# D-class.net
KiCad netlist of a schematic drawn in EAGLE
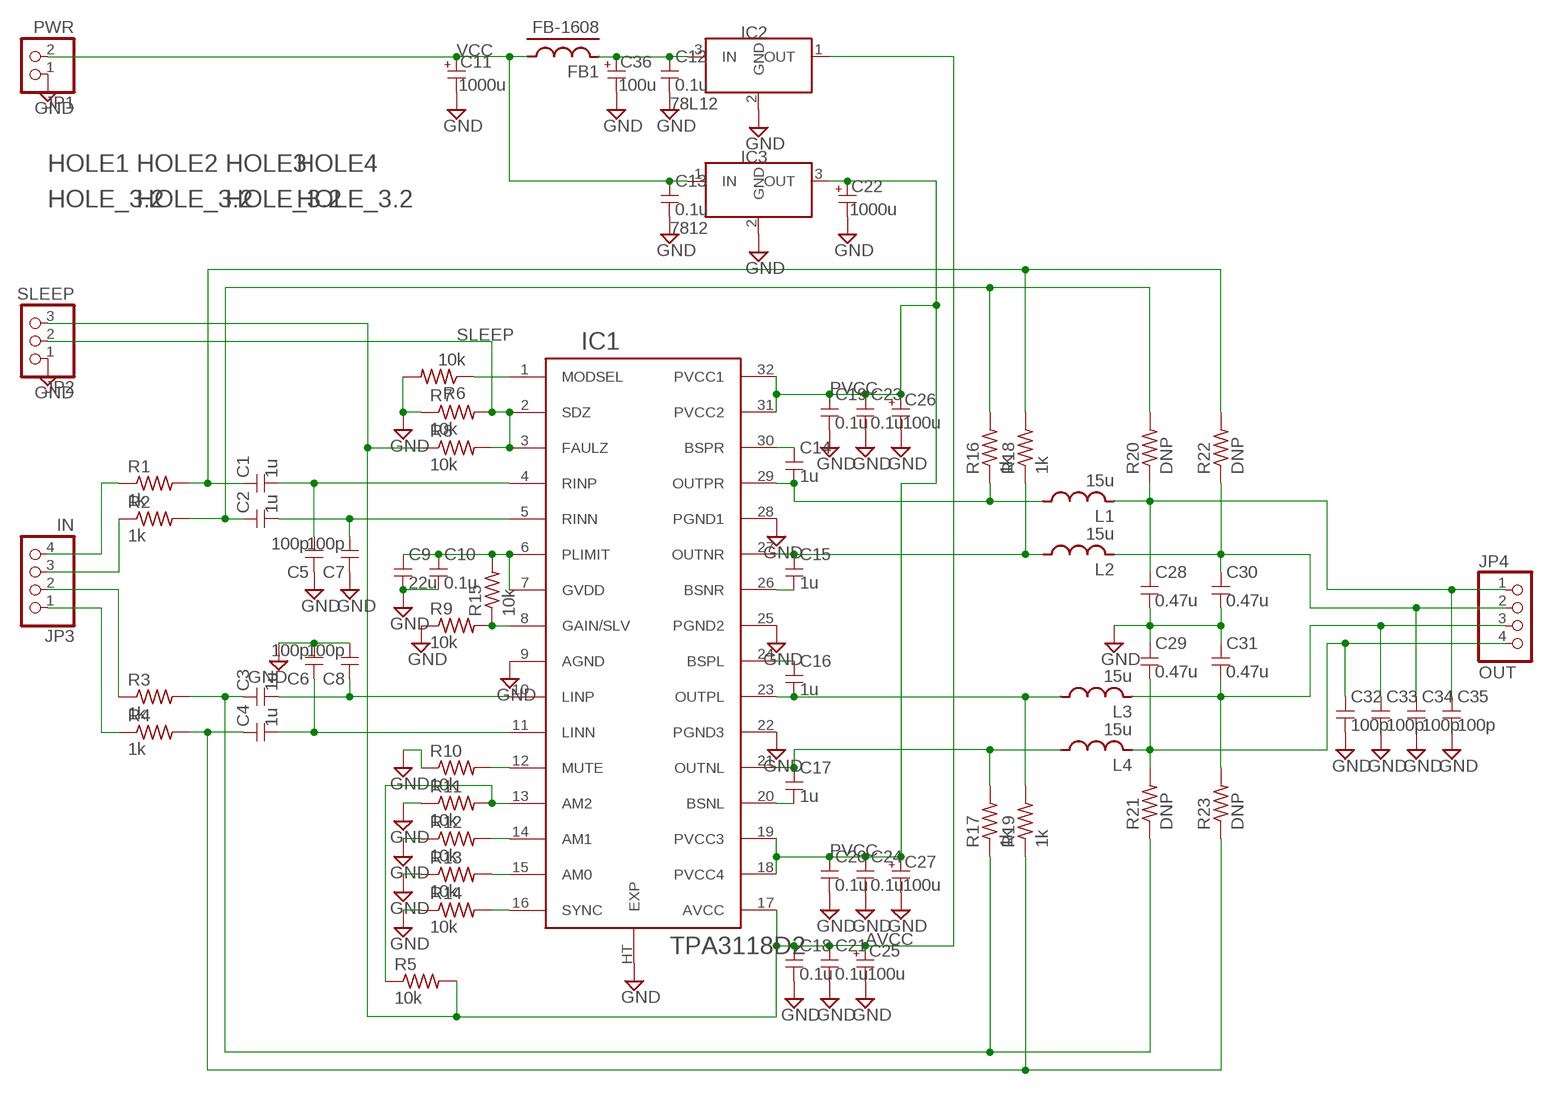
[diagram p0: schematic, sheet 1]

(export (version "E")
  (design (tool "Eeschema 10.0.6"))
  (components
    (comp (ref "C1")
      (value "1u")
      (footprint "eagle-import:3216")
      (libsource (lib "eagle-import") (part "C-3216"))
    )
    (comp (ref "C2")
      (value "1u")
      (footprint "eagle-import:3216")
      (libsource (lib "eagle-import") (part "C-3216"))
    )
    (comp (ref "C3")
      (value "1u")
      (footprint "eagle-import:3216")
      (libsource (lib "eagle-import") (part "C-3216"))
    )
    (comp (ref "C4")
      (value "1u")
      (footprint "eagle-import:3216")
      (libsource (lib "eagle-import") (part "C-3216"))
    )
    (comp (ref "C5")
      (value "100p")
      (footprint "eagle-import:1608")
      (libsource (lib "eagle-import") (part "C-1608"))
    )
    (comp (ref "C6")
      (value "100p")
      (footprint "eagle-import:1608")
      (libsource (lib "eagle-import") (part "C-1608"))
    )
    (comp (ref "C7")
      (value "100p")
      (footprint "eagle-import:1608")
      (libsource (lib "eagle-import") (part "C-1608"))
    )
    (comp (ref "C8")
      (value "100p")
      (footprint "eagle-import:1608")
      (libsource (lib "eagle-import") (part "C-1608"))
    )
    (comp (ref "C9")
      (value "22u")
      (footprint "eagle-import:2012")
      (libsource (lib "eagle-import") (part "C-2012"))
    )
    (comp (ref "C10")
      (value "0.1u")
      (footprint "eagle-import:1608")
      (libsource (lib "eagle-import") (part "C-1608"))
    )
    (comp (ref "C11")
      (value "1000u")
      (footprint "eagle-import:E5-10")
      (libsource (lib "eagle-import") (part "CPOLE5-10"))
    )
    (comp (ref "C12")
      (value "0.1u")
      (footprint "eagle-import:1608")
      (libsource (lib "eagle-import") (part "C-1608"))
    )
    (comp (ref "C13")
      (value "0.1u")
      (footprint "eagle-import:1608")
      (libsource (lib "eagle-import") (part "C-1608"))
    )
    (comp (ref "C14")
      (value "1u")
      (footprint "eagle-import:1608")
      (libsource (lib "eagle-import") (part "C-1608"))
    )
    (comp (ref "C15")
      (value "1u")
      (footprint "eagle-import:1608")
      (libsource (lib "eagle-import") (part "C-1608"))
    )
    (comp (ref "C16")
      (value "1u")
      (footprint "eagle-import:1608")
      (libsource (lib "eagle-import") (part "C-1608"))
    )
    (comp (ref "C17")
      (value "1u")
      (footprint "eagle-import:1608")
      (libsource (lib "eagle-import") (part "C-1608"))
    )
    (comp (ref "C18")
      (value "0.1u")
      (footprint "eagle-import:1608")
      (libsource (lib "eagle-import") (part "C-1608"))
    )
    (comp (ref "C19")
      (value "0.1u")
      (footprint "eagle-import:1608")
      (libsource (lib "eagle-import") (part "C-1608"))
    )
    (comp (ref "C20")
      (value "0.1u")
      (footprint "eagle-import:1608")
      (libsource (lib "eagle-import") (part "C-1608"))
    )
    (comp (ref "C21")
      (value "0.1u")
      (footprint "eagle-import:2012")
      (libsource (lib "eagle-import") (part "C-2012"))
    )
    (comp (ref "C22")
      (value "1000u")
      (footprint "eagle-import:E5-10")
      (libsource (lib "eagle-import") (part "CPOLE5-10"))
    )
    (comp (ref "C23")
      (value "0.1u")
      (footprint "eagle-import:2012")
      (libsource (lib "eagle-import") (part "C-2012"))
    )
    (comp (ref "C24")
      (value "0.1u")
      (footprint "eagle-import:2012")
      (libsource (lib "eagle-import") (part "C-2012"))
    )
    (comp (ref "C25")
      (value "100u")
      (footprint "eagle-import:E2.5-6.5")
      (libsource (lib "eagle-import") (part "CPOLE2.5-6.5"))
    )
    (comp (ref "C26")
      (value "100u")
      (footprint "eagle-import:E2.5-6.5")
      (libsource (lib "eagle-import") (part "CPOLE2.5-6.5"))
    )
    (comp (ref "C27")
      (value "100u")
      (footprint "eagle-import:E2.5-6.5")
      (libsource (lib "eagle-import") (part "CPOLE2.5-6.5"))
    )
    (comp (ref "C28")
      (value "0.47u")
      (footprint "eagle-import:C050-030X075")
      (libsource (lib "eagle-import") (part "C-5"))
    )
    (comp (ref "C29")
      (value "0.47u")
      (footprint "eagle-import:C050-030X075")
      (libsource (lib "eagle-import") (part "C-5"))
    )
    (comp (ref "C30")
      (value "0.47u")
      (footprint "eagle-import:C050-030X075")
      (libsource (lib "eagle-import") (part "C-5"))
    )
    (comp (ref "C31")
      (value "0.47u")
      (footprint "eagle-import:C050-030X075")
      (libsource (lib "eagle-import") (part "C-5"))
    )
    (comp (ref "C32")
      (value "100p")
      (footprint "eagle-import:1608")
      (libsource (lib "eagle-import") (part "C-1608"))
    )
    (comp (ref "C33")
      (value "100p")
      (footprint "eagle-import:1608")
      (libsource (lib "eagle-import") (part "C-1608"))
    )
    (comp (ref "C34")
      (value "100p")
      (footprint "eagle-import:1608")
      (libsource (lib "eagle-import") (part "C-1608"))
    )
    (comp (ref "C35")
      (value "100p")
      (footprint "eagle-import:1608")
      (libsource (lib "eagle-import") (part "C-1608"))
    )
    (comp (ref "C36")
      (value "100u")
      (footprint "eagle-import:E2.5-6.5")
      (libsource (lib "eagle-import") (part "CPOLE2.5-6.5"))
    )
    (comp (ref "FB1")
      (value "FB-1608")
      (footprint "eagle-import:1608")
      (libsource (lib "eagle-import") (part "FB-1608"))
    )
    (comp (ref "HOLE1")
      (value "HOLE_3.2")
      (footprint "eagle-import:HOLE_3.2")
      (libsource (lib "eagle-import") (part "HOLE_3.2"))
    )
    (comp (ref "HOLE2")
      (value "HOLE_3.2")
      (footprint "eagle-import:HOLE_3.2")
      (libsource (lib "eagle-import") (part "HOLE_3.2"))
    )
    (comp (ref "HOLE3")
      (value "HOLE_3.2")
      (footprint "eagle-import:HOLE_3.2")
      (libsource (lib "eagle-import") (part "HOLE_3.2"))
    )
    (comp (ref "HOLE4")
      (value "HOLE_3.2")
      (footprint "eagle-import:HOLE_3.2")
      (libsource (lib "eagle-import") (part "HOLE_3.2"))
    )
    (comp (ref "IC1")
      (value "TPA3118D2")
      (footprint "eagle-import:HTSSOP32DAP")
      (libsource (lib "eagle-import") (part "TPA3118D2"))
    )
    (comp (ref "IC2")
      (value "78L12")
      (footprint "eagle-import:TO-92")
      (libsource (lib "eagle-import") (part "78LX"))
    )
    (comp (ref "IC3")
      (value "7812")
      (footprint "eagle-import:TO-220")
      (libsource (lib "eagle-import") (part "78X-2"))
    )
    (comp (ref "JP1")
      (value "PWR")
      (footprint "eagle-import:1X02")
      (libsource (lib "eagle-import") (part "PINHD-1X2"))
    )
    (comp (ref "JP2")
      (value "SLEEP")
      (footprint "eagle-import:1X03")
      (libsource (lib "eagle-import") (part "PINHD-1X3"))
    )
    (comp (ref "JP3")
      (value "IN")
      (footprint "eagle-import:1X04")
      (libsource (lib "eagle-import") (part "PINHD-1X4"))
    )
    (comp (ref "JP4")
      (value "OUT")
      (footprint "eagle-import:1X04")
      (libsource (lib "eagle-import") (part "PINHD-1X4"))
    )
    (comp (ref "L1")
      (value "15u")
      (footprint "eagle-import:L5-7,5")
      (libsource (lib "eagle-import") (part "L-5"))
    )
    (comp (ref "L2")
      (value "15u")
      (footprint "eagle-import:L5-7,5")
      (libsource (lib "eagle-import") (part "L-5"))
    )
    (comp (ref "L3")
      (value "15u")
      (footprint "eagle-import:L5-7,5")
      (libsource (lib "eagle-import") (part "L-5"))
    )
    (comp (ref "L4")
      (value "15u")
      (footprint "eagle-import:L5-7,5")
      (libsource (lib "eagle-import") (part "L-5"))
    )
    (comp (ref "R1")
      (value "1k")
      (footprint "eagle-import:0207_2V")
      (libsource (lib "eagle-import") (part "R-2.5"))
    )
    (comp (ref "R2")
      (value "1k")
      (footprint "eagle-import:0207_2V")
      (libsource (lib "eagle-import") (part "R-2.5"))
    )
    (comp (ref "R3")
      (value "1k")
      (footprint "eagle-import:0207_2V")
      (libsource (lib "eagle-import") (part "R-2.5"))
    )
    (comp (ref "R4")
      (value "1k")
      (footprint "eagle-import:0207_2V")
      (libsource (lib "eagle-import") (part "R-2.5"))
    )
    (comp (ref "R5")
      (value "10k")
      (footprint "eagle-import:1608")
      (libsource (lib "eagle-import") (part "R-1608"))
    )
    (comp (ref "R6")
      (value "10k")
      (footprint "eagle-import:1608")
      (libsource (lib "eagle-import") (part "R-1608"))
    )
    (comp (ref "R7")
      (value "10k")
      (footprint "eagle-import:1608")
      (libsource (lib "eagle-import") (part "R-1608"))
    )
    (comp (ref "R8")
      (value "10k")
      (footprint "eagle-import:1608")
      (libsource (lib "eagle-import") (part "R-1608"))
    )
    (comp (ref "R9")
      (value "10k")
      (footprint "eagle-import:1608")
      (libsource (lib "eagle-import") (part "R-1608"))
    )
    (comp (ref "R10")
      (value "10k")
      (footprint "eagle-import:1608")
      (libsource (lib "eagle-import") (part "R-1608"))
    )
    (comp (ref "R11")
      (value "10k")
      (footprint "eagle-import:1608")
      (libsource (lib "eagle-import") (part "R-1608"))
    )
    (comp (ref "R12")
      (value "10k")
      (footprint "eagle-import:1608")
      (libsource (lib "eagle-import") (part "R-1608"))
    )
    (comp (ref "R13")
      (value "10k")
      (footprint "eagle-import:1608")
      (libsource (lib "eagle-import") (part "R-1608"))
    )
    (comp (ref "R14")
      (value "10k")
      (footprint "eagle-import:1608")
      (libsource (lib "eagle-import") (part "R-1608"))
    )
    (comp (ref "R15")
      (value "10k")
      (footprint "eagle-import:1608")
      (libsource (lib "eagle-import") (part "R-1608"))
    )
    (comp (ref "R16")
      (value "1k")
      (footprint "eagle-import:0207_2V")
      (libsource (lib "eagle-import") (part "R-2.5"))
    )
    (comp (ref "R17")
      (value "1k")
      (footprint "eagle-import:0207_2V")
      (libsource (lib "eagle-import") (part "R-2.5"))
    )
    (comp (ref "R18")
      (value "1k")
      (footprint "eagle-import:0207_2V")
      (libsource (lib "eagle-import") (part "R-2.5"))
    )
    (comp (ref "R19")
      (value "1k")
      (footprint "eagle-import:0207_2V")
      (libsource (lib "eagle-import") (part "R-2.5"))
    )
    (comp (ref "R20")
      (value "DNP")
      (footprint "eagle-import:0207_2V")
      (libsource (lib "eagle-import") (part "R-2.5"))
    )
    (comp (ref "R21")
      (value "DNP")
      (footprint "eagle-import:0207_2V")
      (libsource (lib "eagle-import") (part "R-2.5"))
    )
    (comp (ref "R22")
      (value "DNP")
      (footprint "eagle-import:0207_2V")
      (libsource (lib "eagle-import") (part "R-2.5"))
    )
    (comp (ref "R23")
      (value "DNP")
      (footprint "eagle-import:0207_2V")
      (libsource (lib "eagle-import") (part "R-2.5"))
    )
  )
  (nets
    (net (code "1") (name "/AVCC") (class "Default")
      (node (ref "C18") (pin "1") (pinfunction "1_1") (pintype "passive"))
      (node (ref "C21") (pin "1") (pinfunction "1_1") (pintype "passive"))
      (node (ref "C25") (pin "+") (pinfunction "1_+") (pintype "passive"))
      (node (ref "IC1") (pin "17") (pinfunction "AVCC_17") (pintype "power_in"))
      (node (ref "IC2") (pin "1") (pinfunction "OUT_1") (pintype "output"))
      (node (ref "JP2") (pin "3") (pinfunction "3_3") (pintype "passive"))
      (node (ref "R5") (pin "2") (pinfunction "2_2") (pintype "passive"))
      (node (ref "R8") (pin "1") (pinfunction "1_1") (pintype "passive"))
    )
    (net (code "2") (name "/PVCC") (class "Default")
      (node (ref "C19") (pin "1") (pinfunction "1_1") (pintype "passive"))
      (node (ref "C20") (pin "1") (pinfunction "1_1") (pintype "passive"))
      (node (ref "C22") (pin "+") (pinfunction "1_+") (pintype "passive"))
      (node (ref "C23") (pin "1") (pinfunction "1_1") (pintype "passive"))
      (node (ref "C24") (pin "1") (pinfunction "1_1") (pintype "passive"))
      (node (ref "C26") (pin "+") (pinfunction "1_+") (pintype "passive"))
      (node (ref "C27") (pin "+") (pinfunction "1_+") (pintype "passive"))
      (node (ref "IC1") (pin "18") (pinfunction "PVCC4_18") (pintype "power_in"))
      (node (ref "IC1") (pin "19") (pinfunction "PVCC3_19") (pintype "power_in"))
      (node (ref "IC1") (pin "31") (pinfunction "PVCC2_31") (pintype "power_in"))
      (node (ref "IC1") (pin "32") (pinfunction "PVCC1_32") (pintype "power_in"))
      (node (ref "IC3") (pin "3") (pinfunction "OUT_3") (pintype "output"))
    )
    (net (code "3") (name "/SLEEP") (class "Default")
      (node (ref "IC1") (pin "2") (pinfunction "SDZ_2") (pintype "input"))
      (node (ref "IC1") (pin "3") (pinfunction "FAULZ_3") (pintype "output"))
      (node (ref "JP2") (pin "2") (pinfunction "2_2") (pintype "passive"))
      (node (ref "R7") (pin "2") (pinfunction "2_2") (pintype "passive"))
      (node (ref "R8") (pin "2") (pinfunction "2_2") (pintype "passive"))
    )
    (net (code "4") (name "/VCC") (class "Default")
      (node (ref "C11") (pin "+") (pinfunction "1_+") (pintype "passive"))
      (node (ref "C13") (pin "1") (pinfunction "1_1") (pintype "passive"))
      (node (ref "FB1") (pin "1") (pinfunction "1_1") (pintype "passive"))
      (node (ref "IC3") (pin "1") (pinfunction "IN_1") (pintype "power_in"))
      (node (ref "JP1") (pin "2") (pinfunction "2_2") (pintype "passive"))
    )
    (net (code "5") (name "GND") (class "Default")
      (node (ref "C10") (pin "2") (pinfunction "2_2") (pintype "passive"))
      (node (ref "C11") (pin "-") (pinfunction "2_-") (pintype "passive"))
      (node (ref "C12") (pin "2") (pinfunction "2_2") (pintype "passive"))
      (node (ref "C13") (pin "2") (pinfunction "2_2") (pintype "passive"))
      (node (ref "C18") (pin "2") (pinfunction "2_2") (pintype "passive"))
      (node (ref "C19") (pin "2") (pinfunction "2_2") (pintype "passive"))
      (node (ref "C20") (pin "2") (pinfunction "2_2") (pintype "passive"))
      (node (ref "C21") (pin "2") (pinfunction "2_2") (pintype "passive"))
      (node (ref "C22") (pin "-") (pinfunction "2_-") (pintype "passive"))
      (node (ref "C23") (pin "2") (pinfunction "2_2") (pintype "passive"))
      (node (ref "C24") (pin "2") (pinfunction "2_2") (pintype "passive"))
      (node (ref "C25") (pin "-") (pinfunction "2_-") (pintype "passive"))
      (node (ref "C26") (pin "-") (pinfunction "2_-") (pintype "passive"))
      (node (ref "C27") (pin "-") (pinfunction "2_-") (pintype "passive"))
      (node (ref "C28") (pin "2") (pinfunction "2_2") (pintype "passive"))
      (node (ref "C29") (pin "1") (pinfunction "1_1") (pintype "passive"))
      (node (ref "C30") (pin "2") (pinfunction "2_2") (pintype "passive"))
      (node (ref "C31") (pin "1") (pinfunction "1_1") (pintype "passive"))
      (node (ref "C32") (pin "2") (pinfunction "2_2") (pintype "passive"))
      (node (ref "C33") (pin "2") (pinfunction "2_2") (pintype "passive"))
      (node (ref "C34") (pin "2") (pinfunction "2_2") (pintype "passive"))
      (node (ref "C35") (pin "2") (pinfunction "2_2") (pintype "passive"))
      (node (ref "C36") (pin "-") (pinfunction "2_-") (pintype "passive"))
      (node (ref "C5") (pin "1") (pinfunction "1_1") (pintype "passive"))
      (node (ref "C6") (pin "2") (pinfunction "2_2") (pintype "passive"))
      (node (ref "C7") (pin "1") (pinfunction "1_1") (pintype "passive"))
      (node (ref "C8") (pin "2") (pinfunction "2_2") (pintype "passive"))
      (node (ref "C9") (pin "2") (pinfunction "2_2") (pintype "passive"))
      (node (ref "IC1") (pin "22") (pinfunction "PGND3_22") (pintype "power_in"))
      (node (ref "IC1") (pin "25") (pinfunction "PGND2_25") (pintype "power_in"))
      (node (ref "IC1") (pin "28") (pinfunction "PGND1_28") (pintype "power_in"))
      (node (ref "IC1") (pin "9") (pinfunction "AGND_9") (pintype "power_in"))
      (node (ref "IC1") (pin "HT") (pinfunction "EXP_HT") (pintype "power_in"))
      (node (ref "IC2") (pin "2") (pinfunction "GND_2") (pintype "power_in"))
      (node (ref "IC3") (pin "2") (pinfunction "GND_2") (pintype "power_in"))
      (node (ref "JP1") (pin "1") (pinfunction "1_1") (pintype "passive"))
      (node (ref "JP2") (pin "1") (pinfunction "1_1") (pintype "passive"))
      (node (ref "R10") (pin "1") (pinfunction "1_1") (pintype "passive"))
      (node (ref "R11") (pin "1") (pinfunction "1_1") (pintype "passive"))
      (node (ref "R12") (pin "1") (pinfunction "1_1") (pintype "passive"))
      (node (ref "R13") (pin "1") (pinfunction "1_1") (pintype "passive"))
      (node (ref "R14") (pin "1") (pinfunction "1_1") (pintype "passive"))
      (node (ref "R6") (pin "2") (pinfunction "2_2") (pintype "passive"))
      (node (ref "R7") (pin "1") (pinfunction "1_1") (pintype "passive"))
      (node (ref "R9") (pin "1") (pinfunction "1_1") (pintype "passive"))
    )
    (net (code "6") (name "Net-(C1-Pad1)") (class "Default")
      (node (ref "C1") (pin "1") (pinfunction "1_1") (pintype "passive"))
      (node (ref "R1") (pin "2") (pinfunction "2_2") (pintype "passive"))
      (node (ref "R18") (pin "2") (pinfunction "2_2") (pintype "passive"))
      (node (ref "R22") (pin "2") (pinfunction "2_2") (pintype "passive"))
    )
    (net (code "7") (name "Net-(C2-Pad1)") (class "Default")
      (node (ref "C2") (pin "1") (pinfunction "1_1") (pintype "passive"))
      (node (ref "R16") (pin "2") (pinfunction "2_2") (pintype "passive"))
      (node (ref "R2") (pin "2") (pinfunction "2_2") (pintype "passive"))
      (node (ref "R20") (pin "2") (pinfunction "2_2") (pintype "passive"))
    )
    (net (code "8") (name "Net-(C3-Pad1)") (class "Default")
      (node (ref "C3") (pin "1") (pinfunction "1_1") (pintype "passive"))
      (node (ref "R17") (pin "1") (pinfunction "1_1") (pintype "passive"))
      (node (ref "R21") (pin "1") (pinfunction "1_1") (pintype "passive"))
      (node (ref "R3") (pin "2") (pinfunction "2_2") (pintype "passive"))
    )
    (net (code "9") (name "Net-(C4-Pad1)") (class "Default")
      (node (ref "C4") (pin "1") (pinfunction "1_1") (pintype "passive"))
      (node (ref "R19") (pin "1") (pinfunction "1_1") (pintype "passive"))
      (node (ref "R23") (pin "1") (pinfunction "1_1") (pintype "passive"))
      (node (ref "R4") (pin "2") (pinfunction "2_2") (pintype "passive"))
    )
    (net (code "10") (name "Net-(C36-1)") (class "Default")
      (node (ref "C12") (pin "1") (pinfunction "1_1") (pintype "passive"))
      (node (ref "C36") (pin "+") (pinfunction "1_+") (pintype "passive"))
      (node (ref "FB1") (pin "2") (pinfunction "2_2") (pintype "passive"))
      (node (ref "IC2") (pin "3") (pinfunction "IN_3") (pintype "power_in"))
    )
    (net (code "11") (name "Net-(IC1-AM0)") (class "Default")
      (node (ref "IC1") (pin "15") (pinfunction "AM0_15") (pintype "input"))
      (node (ref "R13") (pin "2") (pinfunction "2_2") (pintype "passive"))
    )
    (net (code "12") (name "Net-(IC1-AM1)") (class "Default")
      (node (ref "IC1") (pin "14") (pinfunction "AM1_14") (pintype "input"))
      (node (ref "R12") (pin "2") (pinfunction "2_2") (pintype "passive"))
    )
    (net (code "13") (name "Net-(IC1-AM2)") (class "Default")
      (node (ref "IC1") (pin "13") (pinfunction "AM2_13") (pintype "input"))
      (node (ref "R11") (pin "2") (pinfunction "2_2") (pintype "passive"))
      (node (ref "R5") (pin "1") (pinfunction "1_1") (pintype "passive"))
    )
    (net (code "14") (name "Net-(IC1-BSNL)") (class "Default")
      (node (ref "C17") (pin "2") (pinfunction "2_2") (pintype "passive"))
      (node (ref "IC1") (pin "20") (pinfunction "BSNL_20") (pintype "output"))
    )
    (net (code "15") (name "Net-(IC1-BSNR)") (class "Default")
      (node (ref "C15") (pin "2") (pinfunction "2_2") (pintype "passive"))
      (node (ref "IC1") (pin "26") (pinfunction "BSNR_26") (pintype "output"))
    )
    (net (code "16") (name "Net-(IC1-BSPL)") (class "Default")
      (node (ref "C16") (pin "1") (pinfunction "1_1") (pintype "passive"))
      (node (ref "IC1") (pin "24") (pinfunction "BSPL_24") (pintype "input"))
    )
    (net (code "17") (name "Net-(IC1-BSPR)") (class "Default")
      (node (ref "C14") (pin "1") (pinfunction "1_1") (pintype "passive"))
      (node (ref "IC1") (pin "30") (pinfunction "BSPR_30") (pintype "output"))
    )
    (net (code "18") (name "Net-(IC1-GAIN{slash}SLV)") (class "Default")
      (node (ref "IC1") (pin "8") (pinfunction "GAIN/SLV_8") (pintype "input"))
      (node (ref "R15") (pin "1") (pinfunction "1_1") (pintype "passive"))
      (node (ref "R9") (pin "2") (pinfunction "2_2") (pintype "passive"))
    )
    (net (code "19") (name "Net-(IC1-GVDD)") (class "Default")
      (node (ref "C10") (pin "1") (pinfunction "1_1") (pintype "passive"))
      (node (ref "C9") (pin "1") (pinfunction "1_1") (pintype "passive"))
      (node (ref "IC1") (pin "6") (pinfunction "PLIMIT_6") (pintype "input"))
      (node (ref "IC1") (pin "7") (pinfunction "GVDD_7") (pintype "power_in"))
      (node (ref "R15") (pin "2") (pinfunction "2_2") (pintype "passive"))
    )
    (net (code "20") (name "Net-(IC1-LINN)") (class "Default")
      (node (ref "C4") (pin "2") (pinfunction "2_2") (pintype "passive"))
      (node (ref "C6") (pin "1") (pinfunction "1_1") (pintype "passive"))
      (node (ref "IC1") (pin "11") (pinfunction "LINN_11") (pintype "input"))
    )
    (net (code "21") (name "Net-(IC1-LINP)") (class "Default")
      (node (ref "C3") (pin "2") (pinfunction "2_2") (pintype "passive"))
      (node (ref "C8") (pin "1") (pinfunction "1_1") (pintype "passive"))
      (node (ref "IC1") (pin "10") (pinfunction "LINP_10") (pintype "input"))
    )
    (net (code "22") (name "Net-(IC1-MODSEL)") (class "Default")
      (node (ref "IC1") (pin "1") (pinfunction "MODSEL_1") (pintype "input"))
      (node (ref "R6") (pin "1") (pinfunction "1_1") (pintype "passive"))
    )
    (net (code "23") (name "Net-(IC1-MUTE)") (class "Default")
      (node (ref "IC1") (pin "12") (pinfunction "MUTE_12") (pintype "input"))
      (node (ref "R10") (pin "2") (pinfunction "2_2") (pintype "passive"))
    )
    (net (code "24") (name "Net-(IC1-OUTNL)") (class "Default")
      (node (ref "C17") (pin "1") (pinfunction "1_1") (pintype "passive"))
      (node (ref "IC1") (pin "21") (pinfunction "OUTNL_21") (pintype "output"))
      (node (ref "L4") (pin "P$1") (pinfunction "1_P$1") (pintype "passive"))
      (node (ref "R17") (pin "2") (pinfunction "2_2") (pintype "passive"))
    )
    (net (code "25") (name "Net-(IC1-OUTNR)") (class "Default")
      (node (ref "C15") (pin "1") (pinfunction "1_1") (pintype "passive"))
      (node (ref "IC1") (pin "27") (pinfunction "OUTNR_27") (pintype "output"))
      (node (ref "L2") (pin "P$1") (pinfunction "1_P$1") (pintype "passive"))
      (node (ref "R18") (pin "1") (pinfunction "1_1") (pintype "passive"))
    )
    (net (code "26") (name "Net-(IC1-OUTPL)") (class "Default")
      (node (ref "C16") (pin "2") (pinfunction "2_2") (pintype "passive"))
      (node (ref "IC1") (pin "23") (pinfunction "OUTPL_23") (pintype "output"))
      (node (ref "L3") (pin "P$1") (pinfunction "1_P$1") (pintype "passive"))
      (node (ref "R19") (pin "2") (pinfunction "2_2") (pintype "passive"))
    )
    (net (code "27") (name "Net-(IC1-OUTPR)") (class "Default")
      (node (ref "C14") (pin "2") (pinfunction "2_2") (pintype "passive"))
      (node (ref "IC1") (pin "29") (pinfunction "OUTPR_29") (pintype "output"))
      (node (ref "L1") (pin "P$1") (pinfunction "1_P$1") (pintype "passive"))
      (node (ref "R16") (pin "1") (pinfunction "1_1") (pintype "passive"))
    )
    (net (code "28") (name "Net-(IC1-RINN)") (class "Default")
      (node (ref "C2") (pin "2") (pinfunction "2_2") (pintype "passive"))
      (node (ref "C7") (pin "2") (pinfunction "2_2") (pintype "passive"))
      (node (ref "IC1") (pin "5") (pinfunction "RINN_5") (pintype "input"))
    )
    (net (code "29") (name "Net-(IC1-RINP)") (class "Default")
      (node (ref "C1") (pin "2") (pinfunction "2_2") (pintype "passive"))
      (node (ref "C5") (pin "2") (pinfunction "2_2") (pintype "passive"))
      (node (ref "IC1") (pin "4") (pinfunction "RINP_4") (pintype "input"))
    )
    (net (code "30") (name "Net-(IC1-SYNC)") (class "Default")
      (node (ref "IC1") (pin "16") (pinfunction "SYNC_16") (pintype "bidirectional"))
      (node (ref "R14") (pin "2") (pinfunction "2_2") (pintype "passive"))
    )
    (net (code "31") (name "Net-(JP3-Pad1)") (class "Default")
      (node (ref "JP3") (pin "1") (pinfunction "1_1") (pintype "passive"))
      (node (ref "R4") (pin "1") (pinfunction "1_1") (pintype "passive"))
    )
    (net (code "32") (name "Net-(JP3-Pad2)") (class "Default")
      (node (ref "JP3") (pin "2") (pinfunction "2_2") (pintype "passive"))
      (node (ref "R3") (pin "1") (pinfunction "1_1") (pintype "passive"))
    )
    (net (code "33") (name "Net-(JP3-Pad3)") (class "Default")
      (node (ref "JP3") (pin "3") (pinfunction "3_3") (pintype "passive"))
      (node (ref "R2") (pin "1") (pinfunction "1_1") (pintype "passive"))
    )
    (net (code "34") (name "Net-(JP3-Pad4)") (class "Default")
      (node (ref "JP3") (pin "4") (pinfunction "4_4") (pintype "passive"))
      (node (ref "R1") (pin "1") (pinfunction "1_1") (pintype "passive"))
    )
    (net (code "35") (name "Net-(L1-2)") (class "Default")
      (node (ref "C28") (pin "1") (pinfunction "1_1") (pintype "passive"))
      (node (ref "C35") (pin "1") (pinfunction "1_1") (pintype "passive"))
      (node (ref "JP4") (pin "1") (pinfunction "1_1") (pintype "passive"))
      (node (ref "L1") (pin "P$2") (pinfunction "2_P$2") (pintype "passive"))
      (node (ref "R20") (pin "1") (pinfunction "1_1") (pintype "passive"))
    )
    (net (code "36") (name "Net-(L2-2)") (class "Default")
      (node (ref "C30") (pin "1") (pinfunction "1_1") (pintype "passive"))
      (node (ref "C34") (pin "1") (pinfunction "1_1") (pintype "passive"))
      (node (ref "JP4") (pin "2") (pinfunction "2_2") (pintype "passive"))
      (node (ref "L2") (pin "P$2") (pinfunction "2_P$2") (pintype "passive"))
      (node (ref "R22") (pin "1") (pinfunction "1_1") (pintype "passive"))
    )
    (net (code "37") (name "Net-(L3-2)") (class "Default")
      (node (ref "C31") (pin "2") (pinfunction "2_2") (pintype "passive"))
      (node (ref "C33") (pin "1") (pinfunction "1_1") (pintype "passive"))
      (node (ref "JP4") (pin "3") (pinfunction "3_3") (pintype "passive"))
      (node (ref "L3") (pin "P$2") (pinfunction "2_P$2") (pintype "passive"))
      (node (ref "R23") (pin "2") (pinfunction "2_2") (pintype "passive"))
    )
    (net (code "38") (name "Net-(L4-2)") (class "Default")
      (node (ref "C29") (pin "2") (pinfunction "2_2") (pintype "passive"))
      (node (ref "C32") (pin "1") (pinfunction "1_1") (pintype "passive"))
      (node (ref "JP4") (pin "4") (pinfunction "4_4") (pintype "passive"))
      (node (ref "L4") (pin "P$2") (pinfunction "2_P$2") (pintype "passive"))
      (node (ref "R21") (pin "2") (pinfunction "2_2") (pintype "passive"))
    )
  )
)
